# Connectors.net
KiCad netlist of a schematic drawn in Altium Designer
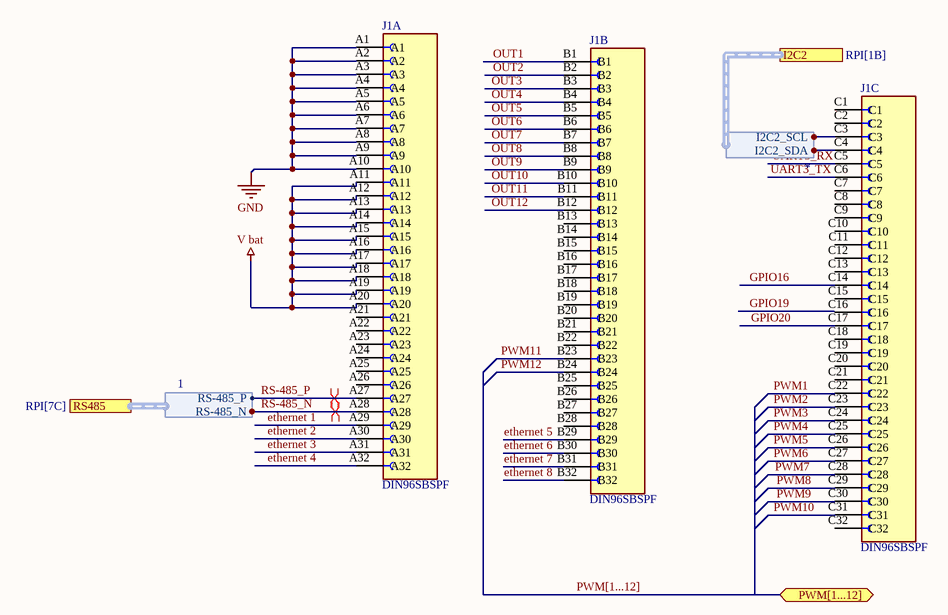
[diagram p0: Connectors.SchDoc]

(export (version "E")
  (design (tool "Eeschema 10.0.6"))
  (components
    (comp (ref "J1")
      (value "DIN96SBSPF")
      (footprint "CINCH_DIN96SBSPF")
      (description "DIN 41612 socket, fully populated, 96 contacts, straight PCB mounted, press-fit pins")
      (fields (field (name "MF") "Cinch Connectivity Solutions"))
      (libsource (lib "DIN96SBSPF") (part "DIN96SBSPF"))
    )
  )
  (nets
    (net (code "5") (name "/GPIO16") (class "Default")
      (node (ref "J1") (pin "C14") (pinfunction "C14_C14") (pintype "passive"))
    )
    (net (code "7") (name "/GPIO20") (class "Default")
      (node (ref "J1") (pin "C17") (pinfunction "C17_C17") (pintype "passive"))
    )
    (net (code "8") (name "/I2C2_SCL") (class "Default")
      (node (ref "J1") (pin "C3") (pinfunction "C3_C3") (pintype "passive"))
    )
    (net (code "9") (name "/I2C2_SDA") (class "Default")
      (node (ref "J1") (pin "C4") (pinfunction "C4_C4") (pintype "passive"))
    )
    (net (code "10") (name "/OUT1") (class "Default")
      (node (ref "J1") (pin "B1") (pinfunction "B1_B1") (pintype "passive"))
    )
    (net (code "11") (name "/OUT2") (class "Default")
      (node (ref "J1") (pin "B2") (pinfunction "B2_B2") (pintype "passive"))
    )
    (net (code "12") (name "/OUT3") (class "Default")
      (node (ref "J1") (pin "B3") (pinfunction "B3_B3") (pintype "passive"))
    )
    (net (code "13") (name "/OUT4") (class "Default")
      (node (ref "J1") (pin "B4") (pinfunction "B4_B4") (pintype "passive"))
    )
    (net (code "14") (name "/OUT5") (class "Default")
      (node (ref "J1") (pin "B5") (pinfunction "B5_B5") (pintype "passive"))
    )
    (net (code "15") (name "/OUT6") (class "Default")
      (node (ref "J1") (pin "B6") (pinfunction "B6_B6") (pintype "passive"))
    )
    (net (code "16") (name "/OUT7") (class "Default")
      (node (ref "J1") (pin "B7") (pinfunction "B7_B7") (pintype "passive"))
    )
    (net (code "17") (name "/OUT8") (class "Default")
      (node (ref "J1") (pin "B8") (pinfunction "B8_B8") (pintype "passive"))
    )
    (net (code "18") (name "/OUT9") (class "Default")
      (node (ref "J1") (pin "B9") (pinfunction "B9_B9") (pintype "passive"))
    )
    (net (code "19") (name "/OUT10") (class "Default")
      (node (ref "J1") (pin "B10") (pinfunction "B10_B10") (pintype "passive"))
    )
    (net (code "20") (name "/OUT11") (class "Default")
      (node (ref "J1") (pin "B11") (pinfunction "B11_B11") (pintype "passive"))
    )
    (net (code "21") (name "/OUT12") (class "Default")
      (node (ref "J1") (pin "B12") (pinfunction "B12_B12") (pintype "passive"))
    )
    (net (code "22") (name "/PWM1") (class "Default")
      (node (ref "J1") (pin "C22") (pinfunction "C22_C22") (pintype "passive"))
    )
    (net (code "23") (name "/PWM2") (class "Default")
      (node (ref "J1") (pin "C23") (pinfunction "C23_C23") (pintype "passive"))
    )
    (net (code "24") (name "/PWM3") (class "Default")
      (node (ref "J1") (pin "C24") (pinfunction "C24_C24") (pintype "passive"))
    )
    (net (code "25") (name "/PWM4") (class "Default")
      (node (ref "J1") (pin "C25") (pinfunction "C25_C25") (pintype "passive"))
    )
    (net (code "26") (name "/PWM5") (class "Default")
      (node (ref "J1") (pin "C26") (pinfunction "C26_C26") (pintype "passive"))
    )
    (net (code "27") (name "/PWM6") (class "Default")
      (node (ref "J1") (pin "C27") (pinfunction "C27_C27") (pintype "passive"))
    )
    (net (code "28") (name "/PWM7") (class "Default")
      (node (ref "J1") (pin "C28") (pinfunction "C28_C28") (pintype "passive"))
    )
    (net (code "29") (name "/PWM8") (class "Default")
      (node (ref "J1") (pin "C29") (pinfunction "C29_C29") (pintype "passive"))
    )
    (net (code "30") (name "/PWM9") (class "Default")
      (node (ref "J1") (pin "C30") (pinfunction "C30_C30") (pintype "passive"))
    )
    (net (code "31") (name "/PWM10") (class "Default")
      (node (ref "J1") (pin "C31") (pinfunction "C31_C31") (pintype "passive"))
    )
    (net (code "32") (name "/PWM11") (class "Default")
      (node (ref "J1") (pin "B23") (pinfunction "B23_B23") (pintype "passive"))
    )
    (net (code "33") (name "/PWM12") (class "Default")
      (node (ref "J1") (pin "B24") (pinfunction "B24_B24") (pintype "passive"))
    )
    (net (code "34") (name "/RS-485_N") (class "Default")
      (node (ref "J1") (pin "A28") (pinfunction "A28_A28") (pintype "passive"))
    )
    (net (code "35") (name "/RS-485_P") (class "Default")
      (node (ref "J1") (pin "A27") (pinfunction "A27_A27") (pintype "passive"))
    )
    (net (code "37") (name "/UART3_RX") (class "Default")
      (node (ref "J1") (pin "C5") (pinfunction "C5_C5") (pintype "passive"))
    )
    (net (code "38") (name "/UART3_TX") (class "Default")
      (node (ref "J1") (pin "C6") (pinfunction "C6_C6") (pintype "passive"))
    )
    (net (code "39") (name "/ethernet 1") (class "Default")
      (node (ref "J1") (pin "A29") (pinfunction "A29_A29") (pintype "passive"))
    )
    (net (code "40") (name "/ethernet 2") (class "Default")
      (node (ref "J1") (pin "A30") (pinfunction "A30_A30") (pintype "passive"))
    )
    (net (code "41") (name "/ethernet 3") (class "Default")
      (node (ref "J1") (pin "A31") (pinfunction "A31_A31") (pintype "passive"))
    )
    (net (code "42") (name "/ethernet 4") (class "Default")
      (node (ref "J1") (pin "A32") (pinfunction "A32_A32") (pintype "passive"))
    )
    (net (code "43") (name "/ethernet 5") (class "Default")
      (node (ref "J1") (pin "B29") (pinfunction "B29_B29") (pintype "passive"))
    )
    (net (code "44") (name "/ethernet 6") (class "Default")
      (node (ref "J1") (pin "B30") (pinfunction "B30_B30") (pintype "passive"))
    )
    (net (code "45") (name "/ethernet 7") (class "Default")
      (node (ref "J1") (pin "B31") (pinfunction "B31_B31") (pintype "passive"))
    )
    (net (code "46") (name "/ethernet 8") (class "Default")
      (node (ref "J1") (pin "B32") (pinfunction "B32_B32") (pintype "passive"))
    )
    (net (code "50") (name "GND") (class "Default")
      (node (ref "J1") (pin "A1") (pinfunction "A1_A1") (pintype "passive"))
      (node (ref "J1") (pin "A10") (pinfunction "A10_A10") (pintype "passive"))
      (node (ref "J1") (pin "A2") (pinfunction "A2_A2") (pintype "passive"))
      (node (ref "J1") (pin "A3") (pinfunction "A3_A3") (pintype "passive"))
      (node (ref "J1") (pin "A4") (pinfunction "A4_A4") (pintype "passive"))
      (node (ref "J1") (pin "A5") (pinfunction "A5_A5") (pintype "passive"))
      (node (ref "J1") (pin "A6") (pinfunction "A6_A6") (pintype "passive"))
      (node (ref "J1") (pin "A7") (pinfunction "A7_A7") (pintype "passive"))
      (node (ref "J1") (pin "A8") (pinfunction "A8_A8") (pintype "passive"))
      (node (ref "J1") (pin "A9") (pinfunction "A9_A9") (pintype "passive"))
    )
    (net (code "51") (name "V bat") (class "Default")
      (node (ref "J1") (pin "A11") (pinfunction "A11_A11") (pintype "passive"))
      (node (ref "J1") (pin "A12") (pinfunction "A12_A12") (pintype "passive"))
      (node (ref "J1") (pin "A13") (pinfunction "A13_A13") (pintype "passive"))
      (node (ref "J1") (pin "A14") (pinfunction "A14_A14") (pintype "passive"))
      (node (ref "J1") (pin "A15") (pinfunction "A15_A15") (pintype "passive"))
      (node (ref "J1") (pin "A16") (pinfunction "A16_A16") (pintype "passive"))
      (node (ref "J1") (pin "A17") (pinfunction "A17_A17") (pintype "passive"))
      (node (ref "J1") (pin "A18") (pinfunction "A18_A18") (pintype "passive"))
      (node (ref "J1") (pin "A19") (pinfunction "A19_A19") (pintype "passive"))
      (node (ref "J1") (pin "A20") (pinfunction "A20_A20") (pintype "passive"))
    )
    (net (code "52") (name "unconnected-(J1-PadA21)") (class "Default")
      (node (ref "J1") (pin "A21") (pinfunction "A21_A21") (pintype "passive"))
    )
    (net (code "53") (name "unconnected-(J1-PadA22)") (class "Default")
      (node (ref "J1") (pin "A22") (pinfunction "A22_A22") (pintype "passive"))
    )
    (net (code "54") (name "unconnected-(J1-PadA23)") (class "Default")
      (node (ref "J1") (pin "A23") (pinfunction "A23_A23") (pintype "passive"))
    )
    (net (code "55") (name "unconnected-(J1-PadA24)") (class "Default")
      (node (ref "J1") (pin "A24") (pinfunction "A24_A24") (pintype "passive"))
    )
    (net (code "56") (name "unconnected-(J1-PadA25)") (class "Default")
      (node (ref "J1") (pin "A25") (pinfunction "A25_A25") (pintype "passive"))
    )
    (net (code "57") (name "unconnected-(J1-PadA26)") (class "Default")
      (node (ref "J1") (pin "A26") (pinfunction "A26_A26") (pintype "passive"))
    )
    (net (code "58") (name "unconnected-(J1-PadB13)") (class "Default")
      (node (ref "J1") (pin "B13") (pinfunction "B13_B13") (pintype "passive"))
    )
    (net (code "59") (name "unconnected-(J1-PadB14)") (class "Default")
      (node (ref "J1") (pin "B14") (pinfunction "B14_B14") (pintype "passive"))
    )
    (net (code "60") (name "unconnected-(J1-PadB15)") (class "Default")
      (node (ref "J1") (pin "B15") (pinfunction "B15_B15") (pintype "passive"))
    )
    (net (code "61") (name "unconnected-(J1-PadB16)") (class "Default")
      (node (ref "J1") (pin "B16") (pinfunction "B16_B16") (pintype "passive"))
    )
    (net (code "62") (name "unconnected-(J1-PadB17)") (class "Default")
      (node (ref "J1") (pin "B17") (pinfunction "B17_B17") (pintype "passive"))
    )
    (net (code "63") (name "unconnected-(J1-PadB18)") (class "Default")
      (node (ref "J1") (pin "B18") (pinfunction "B18_B18") (pintype "passive"))
    )
    (net (code "64") (name "unconnected-(J1-PadB19)") (class "Default")
      (node (ref "J1") (pin "B19") (pinfunction "B19_B19") (pintype "passive"))
    )
    (net (code "65") (name "unconnected-(J1-PadB20)") (class "Default")
      (node (ref "J1") (pin "B20") (pinfunction "B20_B20") (pintype "passive"))
    )
    (net (code "66") (name "unconnected-(J1-PadB21)") (class "Default")
      (node (ref "J1") (pin "B21") (pinfunction "B21_B21") (pintype "passive"))
    )
    (net (code "67") (name "unconnected-(J1-PadB22)") (class "Default")
      (node (ref "J1") (pin "B22") (pinfunction "B22_B22") (pintype "passive"))
    )
    (net (code "68") (name "unconnected-(J1-PadB25)") (class "Default")
      (node (ref "J1") (pin "B25") (pinfunction "B25_B25") (pintype "passive"))
    )
    (net (code "69") (name "unconnected-(J1-PadB26)") (class "Default")
      (node (ref "J1") (pin "B26") (pinfunction "B26_B26") (pintype "passive"))
    )
    (net (code "70") (name "unconnected-(J1-PadB27)") (class "Default")
      (node (ref "J1") (pin "B27") (pinfunction "B27_B27") (pintype "passive"))
    )
    (net (code "71") (name "unconnected-(J1-PadB28)") (class "Default")
      (node (ref "J1") (pin "B28") (pinfunction "B28_B28") (pintype "passive"))
    )
    (net (code "72") (name "unconnected-(J1-PadC1)") (class "Default")
      (node (ref "J1") (pin "C1") (pinfunction "C1_C1") (pintype "passive"))
    )
    (net (code "73") (name "unconnected-(J1-PadC2)") (class "Default")
      (node (ref "J1") (pin "C2") (pinfunction "C2_C2") (pintype "passive"))
    )
    (net (code "74") (name "unconnected-(J1-PadC7)") (class "Default")
      (node (ref "J1") (pin "C7") (pinfunction "C7_C7") (pintype "passive"))
    )
    (net (code "75") (name "unconnected-(J1-PadC8)") (class "Default")
      (node (ref "J1") (pin "C8") (pinfunction "C8_C8") (pintype "passive"))
    )
    (net (code "76") (name "unconnected-(J1-PadC9)") (class "Default")
      (node (ref "J1") (pin "C9") (pinfunction "C9_C9") (pintype "passive"))
    )
    (net (code "77") (name "unconnected-(J1-PadC10)") (class "Default")
      (node (ref "J1") (pin "C10") (pinfunction "C10_C10") (pintype "passive"))
    )
    (net (code "78") (name "unconnected-(J1-PadC11)") (class "Default")
      (node (ref "J1") (pin "C11") (pinfunction "C11_C11") (pintype "passive"))
    )
    (net (code "79") (name "unconnected-(J1-PadC12)") (class "Default")
      (node (ref "J1") (pin "C12") (pinfunction "C12_C12") (pintype "passive"))
    )
    (net (code "80") (name "unconnected-(J1-PadC13)") (class "Default")
      (node (ref "J1") (pin "C13") (pinfunction "C13_C13") (pintype "passive"))
    )
    (net (code "81") (name "unconnected-(J1-PadC15)") (class "Default")
      (node (ref "J1") (pin "C15") (pinfunction "C15_C15") (pintype "passive"))
    )
    (net (code "82") (name "unconnected-(J1-PadC16)") (class "Default")
      (node (ref "J1") (pin "C16") (pinfunction "C16_C16") (pintype "passive"))
    )
    (net (code "83") (name "unconnected-(J1-PadC18)") (class "Default")
      (node (ref "J1") (pin "C18") (pinfunction "C18_C18") (pintype "passive"))
    )
    (net (code "84") (name "unconnected-(J1-PadC19)") (class "Default")
      (node (ref "J1") (pin "C19") (pinfunction "C19_C19") (pintype "passive"))
    )
    (net (code "85") (name "unconnected-(J1-PadC20)") (class "Default")
      (node (ref "J1") (pin "C20") (pinfunction "C20_C20") (pintype "passive"))
    )
    (net (code "86") (name "unconnected-(J1-PadC21)") (class "Default")
      (node (ref "J1") (pin "C21") (pinfunction "C21_C21") (pintype "passive"))
    )
    (net (code "87") (name "unconnected-(J1-PadC32)") (class "Default")
      (node (ref "J1") (pin "C32") (pinfunction "C32_C32") (pintype "passive"))
    )
  )
)
